# diode_sampling_gate_4D.net
KiCad netlist of a schematic drawn in EAGLE
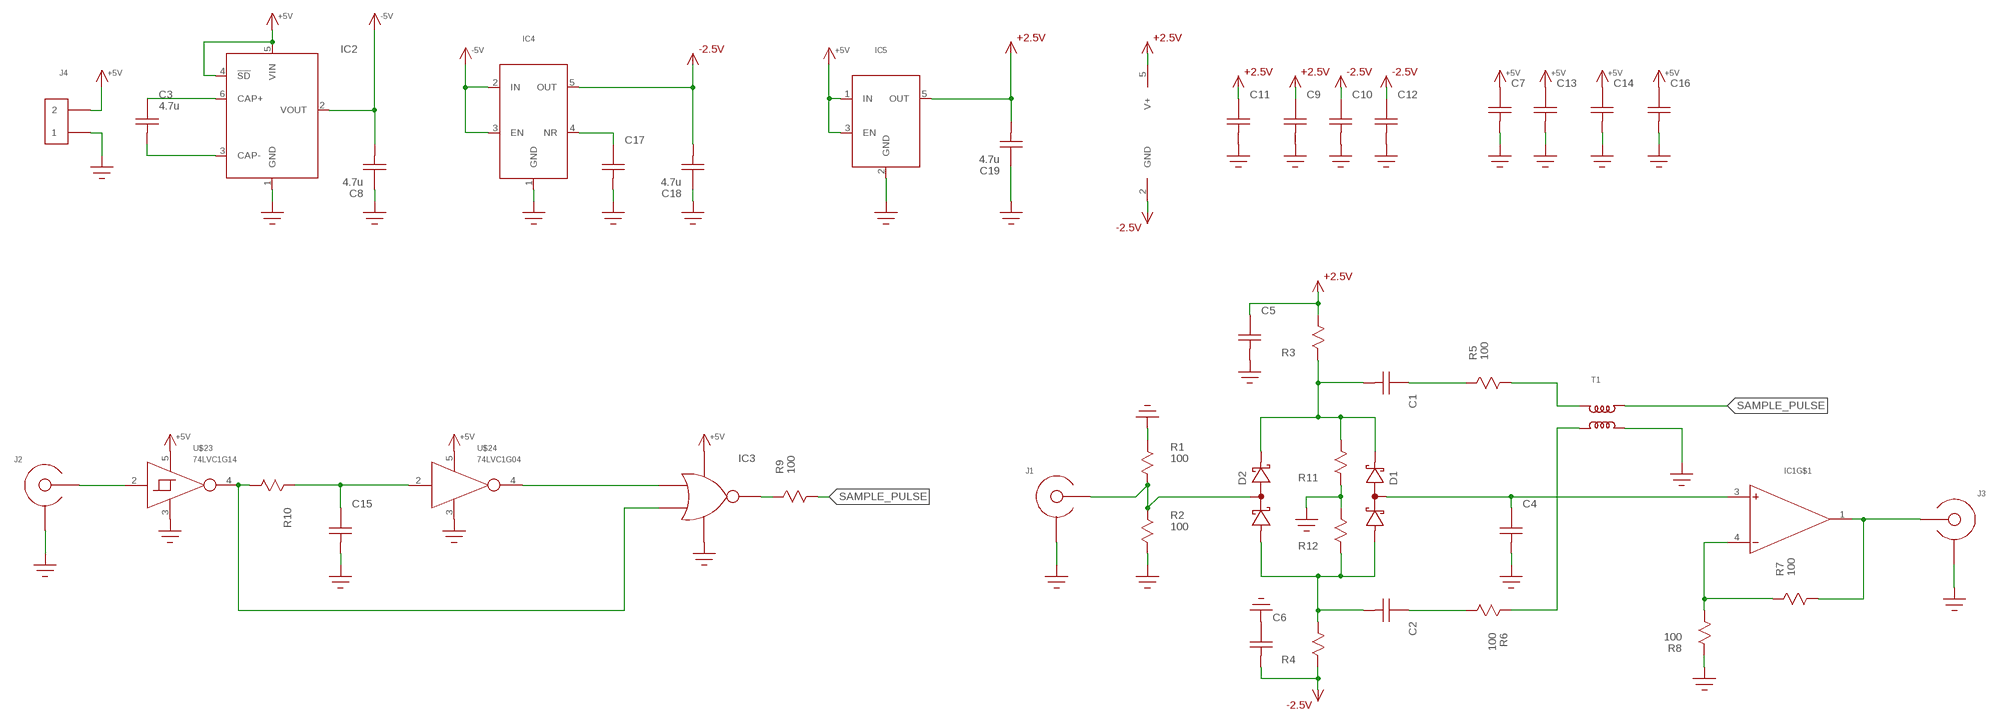
[diagram p0: schematic, sheet 1]

(export (version "E")
  (design (tool "Eeschema 10.0.6"))
  (components
    (comp (ref "C1")
      (value "C0603")
      (footprint "eagle-import:C0603")
      (libsource (lib "eagle-import") (part "C0603"))
    )
    (comp (ref "C2")
      (value "C0603")
      (footprint "eagle-import:C0603")
      (libsource (lib "eagle-import") (part "C0603"))
    )
    (comp (ref "C3")
      (value "4.7u")
      (footprint "eagle-import:0805")
      (libsource (lib "eagle-import") (part "C0805"))
    )
    (comp (ref "C4")
      (value "C0603")
      (footprint "eagle-import:C0603")
      (libsource (lib "eagle-import") (part "C0603"))
    )
    (comp (ref "C5")
      (value "C0603")
      (footprint "eagle-import:C0603")
      (libsource (lib "eagle-import") (part "C0603"))
    )
    (comp (ref "C6")
      (value "C0603")
      (footprint "eagle-import:C0603")
      (libsource (lib "eagle-import") (part "C0603"))
    )
    (comp (ref "C7")
      (value "C0603")
      (footprint "eagle-import:C0603")
      (libsource (lib "eagle-import") (part "C0603"))
    )
    (comp (ref "C8")
      (value "4.7u")
      (footprint "eagle-import:0805")
      (libsource (lib "eagle-import") (part "C0805"))
    )
    (comp (ref "C9")
      (value "C0603")
      (footprint "eagle-import:C0603")
      (libsource (lib "eagle-import") (part "C0603"))
    )
    (comp (ref "C10")
      (value "C0603")
      (footprint "eagle-import:C0603")
      (libsource (lib "eagle-import") (part "C0603"))
    )
    (comp (ref "C11")
      (value "C0805")
      (footprint "eagle-import:0805")
      (libsource (lib "eagle-import") (part "C0805"))
    )
    (comp (ref "C12")
      (value "C0805")
      (footprint "eagle-import:0805")
      (libsource (lib "eagle-import") (part "C0805"))
    )
    (comp (ref "C13")
      (value "C0603")
      (footprint "eagle-import:C0603")
      (libsource (lib "eagle-import") (part "C0603"))
    )
    (comp (ref "C14")
      (value "C0603")
      (footprint "eagle-import:C0603")
      (libsource (lib "eagle-import") (part "C0603"))
    )
    (comp (ref "C15")
      (value "C0603")
      (footprint "eagle-import:C0603")
      (libsource (lib "eagle-import") (part "C0603"))
    )
    (comp (ref "C16")
      (value "C0805")
      (footprint "eagle-import:0805")
      (libsource (lib "eagle-import") (part "C0805"))
    )
    (comp (ref "C17")
      (value "C0603")
      (footprint "eagle-import:C0603")
      (libsource (lib "eagle-import") (part "C0603"))
    )
    (comp (ref "C18")
      (value "4.7u")
      (footprint "eagle-import:0805")
      (libsource (lib "eagle-import") (part "C0805"))
    )
    (comp (ref "C19")
      (value "4.7u")
      (footprint "eagle-import:0805")
      (libsource (lib "eagle-import") (part "C0805"))
    )
    (comp (ref "D1")
      (value "BAS40-04")
      (footprint "eagle-import:SOT-23")
      (libsource (lib "eagle-import") (part "BAS40-04"))
    )
    (comp (ref "D2")
      (value "BAS40-04")
      (footprint "eagle-import:SOT-23")
      (libsource (lib "eagle-import") (part "BAS40-04"))
    )
    (comp (ref "IC1")
      (value "MCP6V81")
      (footprint "eagle-import:SOT23-5")
      (libsource (lib "eagle-import") (part "MCP6V81"))
    )
    (comp (ref "IC2")
      (value "LM2664")
      (footprint "eagle-import:SOT23-6")
      (libsource (lib "eagle-import") (part "LM2664"))
    )
    (comp (ref "IC3")
      (value "74LVC1G02")
      (footprint "eagle-import:SOT23-5")
      (libsource (lib "eagle-import") (part "74LVC1G02"))
    )
    (comp (ref "IC4")
      (value "TPS723XX")
      (footprint "eagle-import:SOT23-5")
      (libsource (lib "eagle-import") (part "TPS723XX"))
    )
    (comp (ref "IC5")
      (value "LP5907")
      (footprint "eagle-import:SOT23-5")
      (libsource (lib "eagle-import") (part "LP5907"))
    )
    (comp (ref "J1")
      (value "EDGE_LAUNCH_JACK")
      (footprint "eagle-import:EDGE_LAUNCH_RF_CON")
      (libsource (lib "eagle-import") (part "EDGE_LAUNCH_JACK"))
    )
    (comp (ref "J2")
      (value "EDGE_LAUNCH_JACK")
      (footprint "eagle-import:EDGE_LAUNCH_RF_CON")
      (libsource (lib "eagle-import") (part "EDGE_LAUNCH_JACK"))
    )
    (comp (ref "J3")
      (value "EDGE_LAUNCH_JACK")
      (footprint "eagle-import:EDGE_LAUNCH_RF_CON")
      (libsource (lib "eagle-import") (part "EDGE_LAUNCH_JACK"))
    )
    (comp (ref "J4")
      (value "HEADER_2PIN")
      (footprint "eagle-import:HEADER_2PIN")
      (libsource (lib "eagle-import") (part "HEADER_2PIN"))
    )
    (comp (ref "R1")
      (value "100")
      (footprint "eagle-import:R0603")
      (libsource (lib "eagle-import") (part "R0603"))
    )
    (comp (ref "R2")
      (value "100")
      (footprint "eagle-import:R0603")
      (libsource (lib "eagle-import") (part "R0603"))
    )
    (comp (ref "R3")
      (value "R0603")
      (footprint "eagle-import:R0603")
      (libsource (lib "eagle-import") (part "R0603"))
    )
    (comp (ref "R4")
      (value "R0603")
      (footprint "eagle-import:R0603")
      (libsource (lib "eagle-import") (part "R0603"))
    )
    (comp (ref "R5")
      (value "100")
      (footprint "eagle-import:R0603")
      (libsource (lib "eagle-import") (part "R0603"))
    )
    (comp (ref "R6")
      (value "100")
      (footprint "eagle-import:R0603")
      (libsource (lib "eagle-import") (part "R0603"))
    )
    (comp (ref "R7")
      (value "100")
      (footprint "eagle-import:R0603")
      (libsource (lib "eagle-import") (part "R0603"))
    )
    (comp (ref "R8")
      (value "100")
      (footprint "eagle-import:R0603")
      (libsource (lib "eagle-import") (part "R0603"))
    )
    (comp (ref "R9")
      (value "100")
      (footprint "eagle-import:R0603")
      (libsource (lib "eagle-import") (part "R0603"))
    )
    (comp (ref "R10")
      (value "R0603")
      (footprint "eagle-import:R0603")
      (libsource (lib "eagle-import") (part "R0603"))
    )
    (comp (ref "R11")
      (value "R0603")
      (footprint "eagle-import:R0603")
      (libsource (lib "eagle-import") (part "R0603"))
    )
    (comp (ref "R12")
      (value "R0603")
      (footprint "eagle-import:R0603")
      (libsource (lib "eagle-import") (part "R0603"))
    )
    (comp (ref "T1")
      (value "MABA007159")
      (footprint "eagle-import:MABAES0061")
      (libsource (lib "eagle-import") (part "MABA007159"))
    )
    (comp (ref "U$23")
      (value "74LVC1G14")
      (footprint "eagle-import:SOT23-5")
      (libsource (lib "eagle-import") (part "74LVC1G14"))
    )
    (comp (ref "U$24")
      (value "74LVC1G04")
      (footprint "eagle-import:SOT23-5")
      (libsource (lib "eagle-import") (part "74LVC1G04"))
    )
  )
  (nets
    (net (code "1") (name "+2.5V") (class "Default")
      (node (ref "C11") (pin "P$2") (pinfunction "P$2_P$2") (pintype "bidirectional"))
      (node (ref "C19") (pin "P$1") (pinfunction "P$1_P$1") (pintype "bidirectional"))
      (node (ref "C5") (pin "P$2") (pinfunction "P$2_P$2") (pintype "bidirectional"))
      (node (ref "C9") (pin "P$2") (pinfunction "P$2_P$2") (pintype "bidirectional"))
      (node (ref "IC1") (pin "5") (pinfunction "V+_5") (pintype "bidirectional"))
      (node (ref "IC5") (pin "5") (pinfunction "OUT_5") (pintype "bidirectional"))
      (node (ref "R3") (pin "P$2") (pinfunction "P$4_P$2") (pintype "bidirectional"))
    )
    (net (code "2") (name "+5V") (class "Default")
      (node (ref "C13") (pin "P$2") (pinfunction "P$2_P$2") (pintype "bidirectional"))
      (node (ref "C14") (pin "P$2") (pinfunction "P$2_P$2") (pintype "bidirectional"))
      (node (ref "C16") (pin "P$2") (pinfunction "P$2_P$2") (pintype "bidirectional"))
      (node (ref "C7") (pin "P$2") (pinfunction "P$2_P$2") (pintype "bidirectional"))
      (node (ref "IC2") (pin "4") (pinfunction "~{SD}_4") (pintype "bidirectional"))
      (node (ref "IC2") (pin "5") (pinfunction "VIN_5") (pintype "bidirectional"))
      (node (ref "IC3") (pin "5") (pinfunction "VCC_5") (pintype "bidirectional"))
      (node (ref "IC5") (pin "1") (pinfunction "IN_1") (pintype "bidirectional"))
      (node (ref "IC5") (pin "3") (pinfunction "EN_3") (pintype "bidirectional"))
      (node (ref "J4") (pin "2") (pinfunction "2_2") (pintype "bidirectional"))
      (node (ref "U$23") (pin "5") (pinfunction "VCC_5") (pintype "bidirectional"))
      (node (ref "U$24") (pin "5") (pinfunction "VCC_5") (pintype "bidirectional"))
    )
    (net (code "3") (name "-2.5V") (class "Default")
      (node (ref "C10") (pin "P$2") (pinfunction "P$2_P$2") (pintype "bidirectional"))
      (node (ref "C12") (pin "P$2") (pinfunction "P$2_P$2") (pintype "bidirectional"))
      (node (ref "C18") (pin "P$1") (pinfunction "P$1_P$1") (pintype "bidirectional"))
      (node (ref "C6") (pin "P$1") (pinfunction "P$1_P$1") (pintype "bidirectional"))
      (node (ref "IC1") (pin "2") (pinfunction "GND_2") (pintype "bidirectional"))
      (node (ref "IC4") (pin "5") (pinfunction "OUT_5") (pintype "bidirectional"))
      (node (ref "R4") (pin "P$1") (pinfunction "P$3_P$1") (pintype "bidirectional"))
    )
    (net (code "4") (name "-5V") (class "Default")
      (node (ref "C8") (pin "P$1") (pinfunction "P$1_P$1") (pintype "bidirectional"))
      (node (ref "IC2") (pin "2") (pinfunction "VOUT_2") (pintype "bidirectional"))
      (node (ref "IC4") (pin "2") (pinfunction "IN_2") (pintype "bidirectional"))
      (node (ref "IC4") (pin "3") (pinfunction "EN_3") (pintype "bidirectional"))
    )
    (net (code "5") (name "GND") (class "Default")
      (node (ref "C10") (pin "P$1") (pinfunction "P$1_P$1") (pintype "bidirectional"))
      (node (ref "C11") (pin "P$1") (pinfunction "P$1_P$1") (pintype "bidirectional"))
      (node (ref "C12") (pin "P$1") (pinfunction "P$1_P$1") (pintype "bidirectional"))
      (node (ref "C13") (pin "P$1") (pinfunction "P$1_P$1") (pintype "bidirectional"))
      (node (ref "C14") (pin "P$1") (pinfunction "P$1_P$1") (pintype "bidirectional"))
      (node (ref "C15") (pin "P$1") (pinfunction "P$1_P$1") (pintype "bidirectional"))
      (node (ref "C16") (pin "P$1") (pinfunction "P$1_P$1") (pintype "bidirectional"))
      (node (ref "C17") (pin "P$1") (pinfunction "P$1_P$1") (pintype "bidirectional"))
      (node (ref "C18") (pin "P$2") (pinfunction "P$2_P$2") (pintype "bidirectional"))
      (node (ref "C19") (pin "P$2") (pinfunction "P$2_P$2") (pintype "bidirectional"))
      (node (ref "C4") (pin "P$1") (pinfunction "P$1_P$1") (pintype "bidirectional"))
      (node (ref "C5") (pin "P$1") (pinfunction "P$1_P$1") (pintype "bidirectional"))
      (node (ref "C6") (pin "P$2") (pinfunction "P$2_P$2") (pintype "bidirectional"))
      (node (ref "C7") (pin "P$1") (pinfunction "P$1_P$1") (pintype "bidirectional"))
      (node (ref "C8") (pin "P$2") (pinfunction "P$2_P$2") (pintype "bidirectional"))
      (node (ref "C9") (pin "P$1") (pinfunction "P$1_P$1") (pintype "bidirectional"))
      (node (ref "IC2") (pin "1") (pinfunction "GND_1") (pintype "bidirectional"))
      (node (ref "IC3") (pin "3") (pinfunction "GND_3") (pintype "bidirectional"))
      (node (ref "IC4") (pin "1") (pinfunction "GND_1") (pintype "bidirectional"))
      (node (ref "IC5") (pin "2") (pinfunction "GND_2") (pintype "bidirectional"))
      (node (ref "J1") (pin "GND@1") (pinfunction "SHIELD_GND@1") (pintype "bidirectional"))
      (node (ref "J1") (pin "GND@10") (pinfunction "SHIELD_GND@10") (pintype "bidirectional"))
      (node (ref "J1") (pin "GND@11") (pinfunction "SHIELD_GND@11") (pintype "bidirectional"))
      (node (ref "J1") (pin "GND@12") (pinfunction "SHIELD_GND@12") (pintype "bidirectional"))
      (node (ref "J1") (pin "GND@2") (pinfunction "SHIELD_GND@2") (pintype "bidirectional"))
      (node (ref "J1") (pin "GND@3") (pinfunction "SHIELD_GND@3") (pintype "bidirectional"))
      (node (ref "J1") (pin "GND@4") (pinfunction "SHIELD_GND@4") (pintype "bidirectional"))
      (node (ref "J1") (pin "GND@5") (pinfunction "SHIELD_GND@5") (pintype "bidirectional"))
      (node (ref "J1") (pin "GND@6") (pinfunction "SHIELD_GND@6") (pintype "bidirectional"))
      (node (ref "J1") (pin "GND@7") (pinfunction "SHIELD_GND@7") (pintype "bidirectional"))
      (node (ref "J1") (pin "GND@8") (pinfunction "SHIELD_GND@8") (pintype "bidirectional"))
      (node (ref "J1") (pin "GND@9") (pinfunction "SHIELD_GND@9") (pintype "bidirectional"))
      (node (ref "J1") (pin "SHIELD@1") (pinfunction "SHIELD_SHIELD@1") (pintype "bidirectional"))
      (node (ref "J1") (pin "SHIELD@2") (pinfunction "SHIELD_SHIELD@2") (pintype "bidirectional"))
      (node (ref "J2") (pin "GND@1") (pinfunction "SHIELD_GND@1") (pintype "bidirectional"))
      (node (ref "J2") (pin "GND@10") (pinfunction "SHIELD_GND@10") (pintype "bidirectional"))
      (node (ref "J2") (pin "GND@11") (pinfunction "SHIELD_GND@11") (pintype "bidirectional"))
      (node (ref "J2") (pin "GND@12") (pinfunction "SHIELD_GND@12") (pintype "bidirectional"))
      (node (ref "J2") (pin "GND@2") (pinfunction "SHIELD_GND@2") (pintype "bidirectional"))
      (node (ref "J2") (pin "GND@3") (pinfunction "SHIELD_GND@3") (pintype "bidirectional"))
      (node (ref "J2") (pin "GND@4") (pinfunction "SHIELD_GND@4") (pintype "bidirectional"))
      (node (ref "J2") (pin "GND@5") (pinfunction "SHIELD_GND@5") (pintype "bidirectional"))
      (node (ref "J2") (pin "GND@6") (pinfunction "SHIELD_GND@6") (pintype "bidirectional"))
      (node (ref "J2") (pin "GND@7") (pinfunction "SHIELD_GND@7") (pintype "bidirectional"))
      (node (ref "J2") (pin "GND@8") (pinfunction "SHIELD_GND@8") (pintype "bidirectional"))
      (node (ref "J2") (pin "GND@9") (pinfunction "SHIELD_GND@9") (pintype "bidirectional"))
      (node (ref "J2") (pin "SHIELD@1") (pinfunction "SHIELD_SHIELD@1") (pintype "bidirectional"))
      (node (ref "J2") (pin "SHIELD@2") (pinfunction "SHIELD_SHIELD@2") (pintype "bidirectional"))
      (node (ref "J3") (pin "GND@1") (pinfunction "SHIELD_GND@1") (pintype "bidirectional"))
      (node (ref "J3") (pin "GND@10") (pinfunction "SHIELD_GND@10") (pintype "bidirectional"))
      (node (ref "J3") (pin "GND@11") (pinfunction "SHIELD_GND@11") (pintype "bidirectional"))
      (node (ref "J3") (pin "GND@12") (pinfunction "SHIELD_GND@12") (pintype "bidirectional"))
      (node (ref "J3") (pin "GND@2") (pinfunction "SHIELD_GND@2") (pintype "bidirectional"))
      (node (ref "J3") (pin "GND@3") (pinfunction "SHIELD_GND@3") (pintype "bidirectional"))
      (node (ref "J3") (pin "GND@4") (pinfunction "SHIELD_GND@4") (pintype "bidirectional"))
      (node (ref "J3") (pin "GND@5") (pinfunction "SHIELD_GND@5") (pintype "bidirectional"))
      (node (ref "J3") (pin "GND@6") (pinfunction "SHIELD_GND@6") (pintype "bidirectional"))
      (node (ref "J3") (pin "GND@7") (pinfunction "SHIELD_GND@7") (pintype "bidirectional"))
      (node (ref "J3") (pin "GND@8") (pinfunction "SHIELD_GND@8") (pintype "bidirectional"))
      (node (ref "J3") (pin "GND@9") (pinfunction "SHIELD_GND@9") (pintype "bidirectional"))
      (node (ref "J3") (pin "SHIELD@1") (pinfunction "SHIELD_SHIELD@1") (pintype "bidirectional"))
      (node (ref "J3") (pin "SHIELD@2") (pinfunction "SHIELD_SHIELD@2") (pintype "bidirectional"))
      (node (ref "J4") (pin "1") (pinfunction "1_1") (pintype "bidirectional"))
      (node (ref "R1") (pin "P$1") (pinfunction "P$3_P$1") (pintype "bidirectional"))
      (node (ref "R11") (pin "P$1") (pinfunction "P$3_P$1") (pintype "bidirectional"))
      (node (ref "R12") (pin "P$2") (pinfunction "P$4_P$2") (pintype "bidirectional"))
      (node (ref "R2") (pin "P$2") (pinfunction "P$4_P$2") (pintype "bidirectional"))
      (node (ref "R8") (pin "P$1") (pinfunction "P$3_P$1") (pintype "bidirectional"))
      (node (ref "T1") (pin "3") (pinfunction "3_3") (pintype "bidirectional"))
      (node (ref "U$23") (pin "3") (pinfunction "GND_3") (pintype "bidirectional"))
      (node (ref "U$24") (pin "3") (pinfunction "GND_3") (pintype "bidirectional"))
    )
    (net (code "6") (name "Net-(D1-ANODE)") (class "Default")
      (node (ref "C2") (pin "P$1") (pinfunction "P$1_P$1") (pintype "bidirectional"))
      (node (ref "D1") (pin "1") (pinfunction "ANODE_1") (pintype "bidirectional"))
      (node (ref "D2") (pin "1") (pinfunction "ANODE_1") (pintype "bidirectional"))
      (node (ref "R12") (pin "P$1") (pinfunction "P$3_P$1") (pintype "bidirectional"))
      (node (ref "R4") (pin "P$2") (pinfunction "P$4_P$2") (pintype "bidirectional"))
    )
    (net (code "7") (name "Net-(D1-CATHODE)") (class "Default")
      (node (ref "C1") (pin "P$1") (pinfunction "P$1_P$1") (pintype "bidirectional"))
      (node (ref "D1") (pin "2") (pinfunction "CATHODE_2") (pintype "bidirectional"))
      (node (ref "D2") (pin "2") (pinfunction "CATHODE_2") (pintype "bidirectional"))
      (node (ref "R11") (pin "P$2") (pinfunction "P$4_P$2") (pintype "bidirectional"))
      (node (ref "R3") (pin "P$1") (pinfunction "P$3_P$1") (pintype "bidirectional"))
    )
    (net (code "8") (name "Net-(D1-COMMON)") (class "Default")
      (node (ref "C4") (pin "P$2") (pinfunction "P$2_P$2") (pintype "bidirectional"))
      (node (ref "D1") (pin "3") (pinfunction "COMMON_3") (pintype "bidirectional"))
      (node (ref "IC1") (pin "3") (pinfunction "+_3") (pintype "bidirectional"))
    )
    (net (code "9") (name "Net-(D2-COMMON)") (class "Default")
      (node (ref "D2") (pin "3") (pinfunction "COMMON_3") (pintype "bidirectional"))
      (node (ref "J1") (pin "CENTER") (pinfunction "CENTER_CENTER") (pintype "bidirectional"))
      (node (ref "R1") (pin "P$2") (pinfunction "P$4_P$2") (pintype "bidirectional"))
      (node (ref "R2") (pin "P$1") (pinfunction "P$3_P$1") (pintype "bidirectional"))
    )
    (net (code "10") (name "Net-(IC1A--)") (class "Default")
      (node (ref "IC1") (pin "4") (pinfunction "-_4") (pintype "bidirectional"))
      (node (ref "R7") (pin "P$1") (pinfunction "P$3_P$1") (pintype "bidirectional"))
      (node (ref "R8") (pin "P$2") (pinfunction "P$4_P$2") (pintype "bidirectional"))
    )
    (net (code "11") (name "Net-(IC1A-OUT)") (class "Default")
      (node (ref "IC1") (pin "1") (pinfunction "OUT_1") (pintype "bidirectional"))
      (node (ref "J3") (pin "CENTER") (pinfunction "CENTER_CENTER") (pintype "bidirectional"))
      (node (ref "R7") (pin "P$2") (pinfunction "P$4_P$2") (pintype "bidirectional"))
    )
    (net (code "12") (name "Net-(IC2-CAP+)") (class "Default")
      (node (ref "C3") (pin "P$2") (pinfunction "P$2_P$2") (pintype "bidirectional"))
      (node (ref "IC2") (pin "6") (pinfunction "CAP+_6") (pintype "bidirectional"))
    )
    (net (code "13") (name "Net-(IC2-CAP-)") (class "Default")
      (node (ref "C3") (pin "P$1") (pinfunction "P$1_P$1") (pintype "bidirectional"))
      (node (ref "IC2") (pin "3") (pinfunction "CAP-_3") (pintype "bidirectional"))
    )
    (net (code "14") (name "Net-(IC3-A)") (class "Default")
      (node (ref "IC3") (pin "1") (pinfunction "A_1") (pintype "bidirectional"))
      (node (ref "U$24") (pin "4") (pinfunction "OUT_4") (pintype "bidirectional"))
    )
    (net (code "15") (name "Net-(IC3-B)") (class "Default")
      (node (ref "IC3") (pin "2") (pinfunction "B_2") (pintype "bidirectional"))
      (node (ref "R10") (pin "P$2") (pinfunction "P$4_P$2") (pintype "bidirectional"))
      (node (ref "U$23") (pin "4") (pinfunction "OUT_4") (pintype "bidirectional"))
    )
    (net (code "16") (name "Net-(IC3-Y)") (class "Default")
      (node (ref "IC3") (pin "4") (pinfunction "Y_4") (pintype "bidirectional"))
      (node (ref "R9") (pin "P$1") (pinfunction "P$3_P$1") (pintype "bidirectional"))
    )
    (net (code "17") (name "Net-(IC4-NR)") (class "Default")
      (node (ref "C17") (pin "P$2") (pinfunction "P$2_P$2") (pintype "bidirectional"))
      (node (ref "IC4") (pin "4") (pinfunction "NR_4") (pintype "bidirectional"))
    )
    (net (code "18") (name "Net-(R5-P$3)") (class "Default")
      (node (ref "C1") (pin "P$2") (pinfunction "P$2_P$2") (pintype "bidirectional"))
      (node (ref "R5") (pin "P$1") (pinfunction "P$3_P$1") (pintype "bidirectional"))
    )
    (net (code "19") (name "Net-(R5-P$4)") (class "Default")
      (node (ref "R5") (pin "P$2") (pinfunction "P$4_P$2") (pintype "bidirectional"))
      (node (ref "T1") (pin "5") (pinfunction "5_5") (pintype "bidirectional"))
    )
    (net (code "20") (name "Net-(R6-P$3)") (class "Default")
      (node (ref "R6") (pin "P$1") (pinfunction "P$3_P$1") (pintype "bidirectional"))
      (node (ref "T1") (pin "4") (pinfunction "4_4") (pintype "bidirectional"))
    )
    (net (code "21") (name "Net-(R6-P$4)") (class "Default")
      (node (ref "C2") (pin "P$2") (pinfunction "P$2_P$2") (pintype "bidirectional"))
      (node (ref "R6") (pin "P$2") (pinfunction "P$4_P$2") (pintype "bidirectional"))
    )
    (net (code "22") (name "Net-(R10-P$3)") (class "Default")
      (node (ref "C15") (pin "P$2") (pinfunction "P$2_P$2") (pintype "bidirectional"))
      (node (ref "R10") (pin "P$1") (pinfunction "P$3_P$1") (pintype "bidirectional"))
      (node (ref "U$24") (pin "2") (pinfunction "IN_2") (pintype "bidirectional"))
    )
    (net (code "23") (name "Net-(U$23-IN)") (class "Default")
      (node (ref "J2") (pin "CENTER") (pinfunction "CENTER_CENTER") (pintype "bidirectional"))
      (node (ref "U$23") (pin "2") (pinfunction "IN_2") (pintype "bidirectional"))
    )
    (net (code "24") (name "SAMPLE_PULSE") (class "Default")
      (node (ref "R9") (pin "P$2") (pinfunction "P$4_P$2") (pintype "bidirectional"))
      (node (ref "T1") (pin "1") (pinfunction "1_1") (pintype "bidirectional"))
    )
  )
)
